# MOTORDEMO.net
KiCad netlist of a schematic drawn in Altium Designer
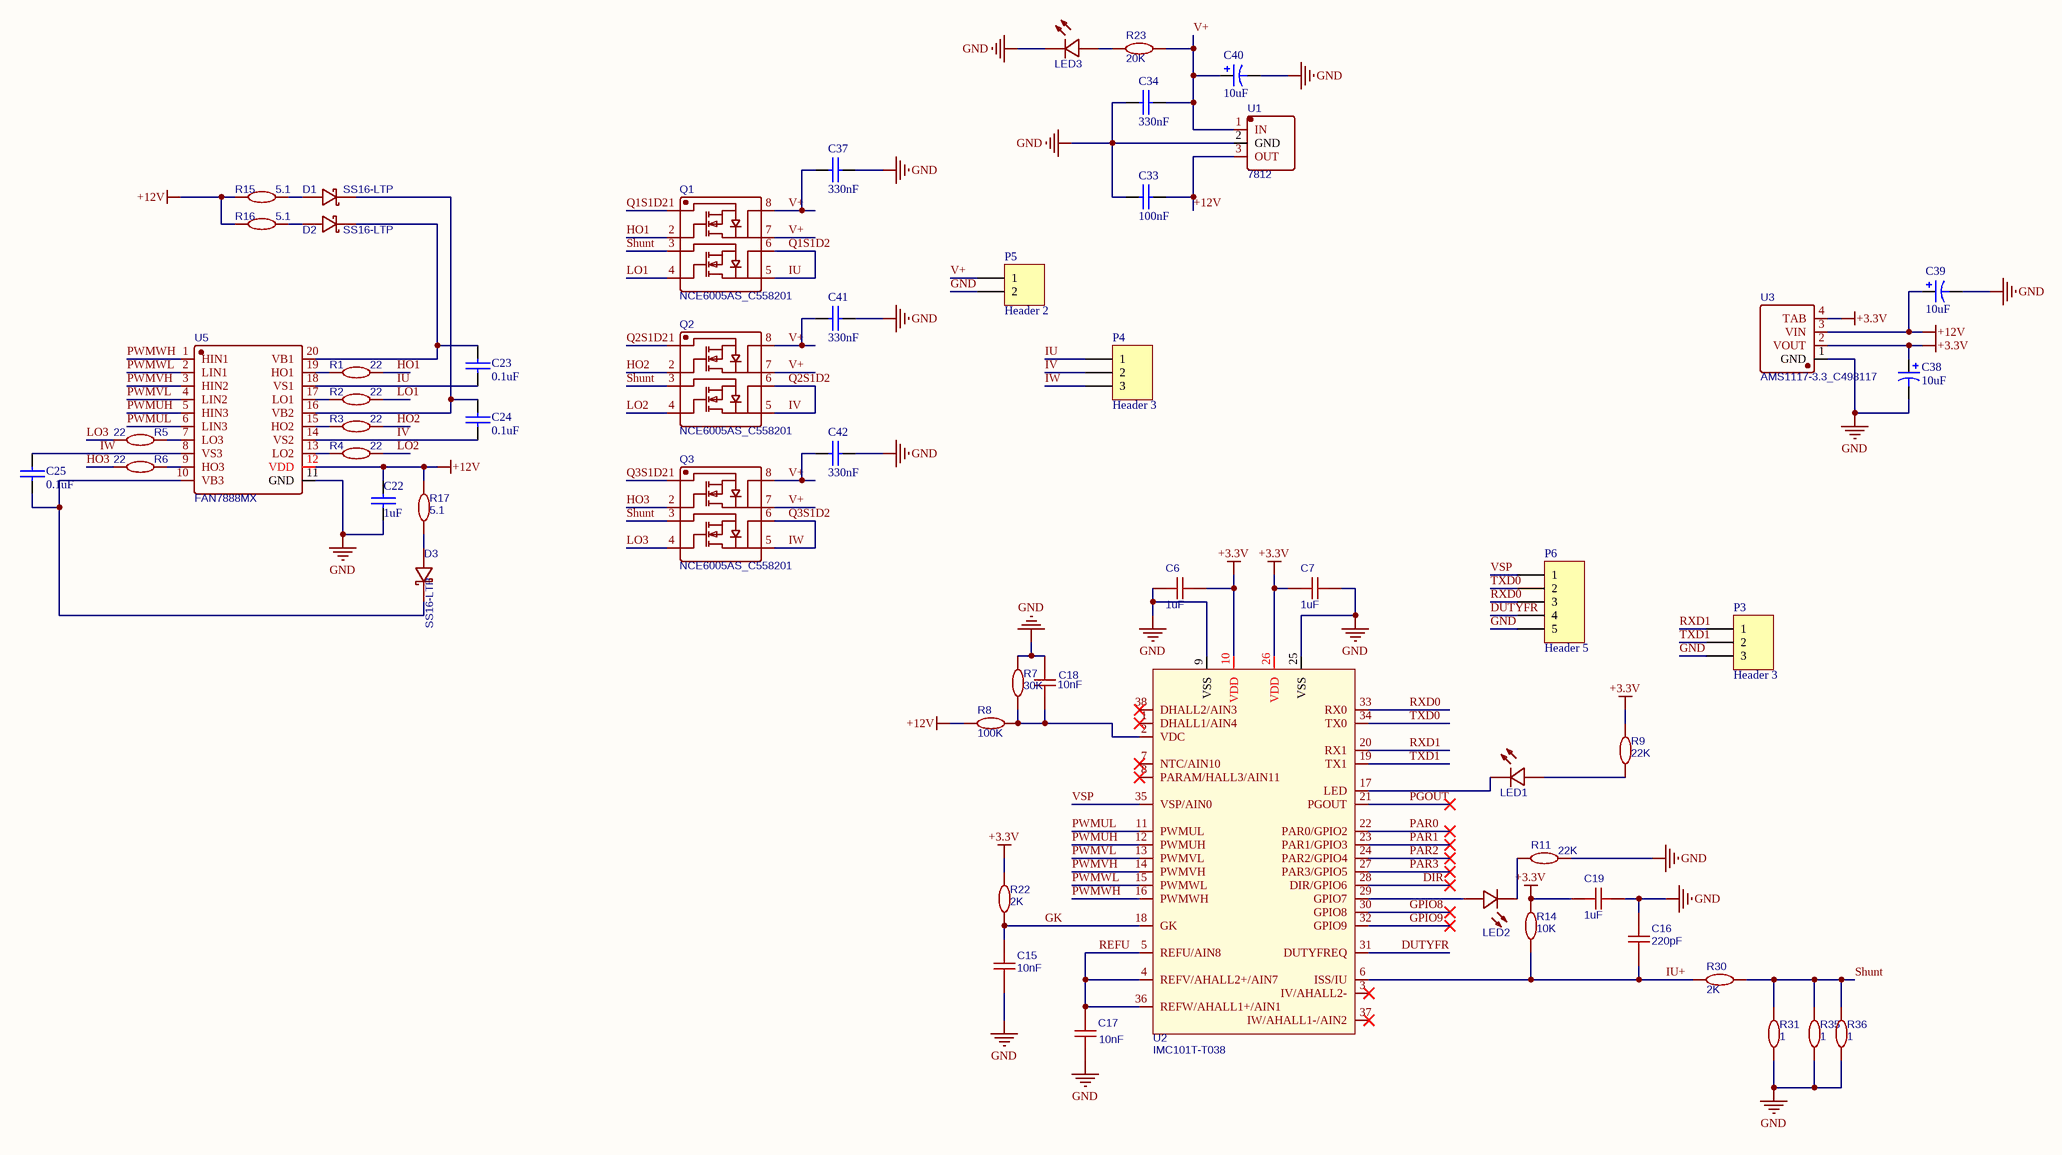
[diagram p0: MOTORDEMO.SchDoc]

(export (version "E")
  (design (tool "Eeschema 10.0.6"))
  (components
    (comp (ref "C6")
      (value "1uF")
      (footprint "C0603")
      (fields
        (field (name "BOM_MANUFACTURER PART") "CL10B104KC8NNNC")
        (field (name "BOM_SUPPLIER PART") "C15725")
      )
      (libsource (lib "motor") (part "100nF"))
    )
    (comp (ref "C7")
      (value "1uF")
      (footprint "C0603")
      (fields
        (field (name "BOM_MANUFACTURER PART") "CL10B104KC8NNNC")
        (field (name "BOM_SUPPLIER PART") "C15725")
      )
      (libsource (lib "motor") (part "100nF"))
    )
    (comp (ref "C15")
      (value "10nF")
      (footprint "C0603")
      (fields
        (field (name "BOM_MANUFACTURER PART") "CL10B104KC8NNNC")
        (field (name "BOM_SUPPLIER PART") "C15725")
      )
      (libsource (lib "motor") (part "100nF"))
    )
    (comp (ref "C16")
      (value "220pF")
      (footprint "C0603")
      (fields
        (field (name "BOM_MANUFACTURER PART") "CL10B104KC8NNNC")
        (field (name "BOM_SUPPLIER PART") "C15725")
      )
      (libsource (lib "motor") (part "100nF"))
    )
    (comp (ref "C17")
      (value "10nF")
      (footprint "C0603")
      (fields
        (field (name "BOM_MANUFACTURER PART") "CL10B104KC8NNNC")
        (field (name "BOM_SUPPLIER PART") "C15725")
      )
      (libsource (lib "motor") (part "100nF"))
    )
    (comp (ref "C18")
      (value "10nF")
      (footprint "C0603")
      (fields
        (field (name "BOM_MANUFACTURER PART") "CL10B104KC8NNNC")
        (field (name "BOM_SUPPLIER PART") "C15725")
      )
      (libsource (lib "motor") (part "100nF"))
    )
    (comp (ref "C19")
      (value "1uF")
      (footprint "C0603")
      (fields
        (field (name "BOM_MANUFACTURER PART") "CL10B104KC8NNNC")
        (field (name "BOM_SUPPLIER PART") "C15725")
      )
      (libsource (lib "motor") (part "100nF"))
    )
    (comp (ref "C22")
      (value "1uF")
      (footprint "C 0603_L")
      (description "Capacitor")
      (libsource (lib "原理图库") (part "CAP"))
    )
    (comp (ref "C23")
      (value "0.1uF")
      (footprint "C 0603_L")
      (description "Capacitor")
      (libsource (lib "原理图库") (part "CAP"))
    )
    (comp (ref "C24")
      (value "0.1uF")
      (footprint "C 0603_L")
      (description "Capacitor")
      (libsource (lib "原理图库") (part "CAP"))
    )
    (comp (ref "C25")
      (value "0.1uF")
      (footprint "C 0603_L")
      (description "Capacitor")
      (libsource (lib "原理图库") (part "CAP"))
    )
    (comp (ref "C33")
      (value "100nF")
      (footprint "C 0603_L")
      (description "Capacitor")
      (libsource (lib "原理图库") (part "CAP"))
    )
    (comp (ref "C34")
      (value "330nF")
      (footprint "C 0603_L")
      (description "Capacitor")
      (libsource (lib "原理图库") (part "CAP"))
    )
    (comp (ref "C37")
      (value "330nF")
      (footprint "C 0603_L")
      (description "Capacitor")
      (libsource (lib "原理图库") (part "CAP"))
    )
    (comp (ref "C38")
      (value "10uF")
      (footprint "10uF,35V,cap4*5.4")
      (description "Polarized Capacitor (Surface Mount)")
      (fields (field (name "PUBLISHER") "Altium Limited"))
      (libsource (lib "Miscellaneous Devices") (part "Cap Pol3"))
    )
    (comp (ref "C39")
      (value "10uF")
      (footprint "10uF,35V,cap4*5.4")
      (description "Polarized Capacitor (Surface Mount)")
      (fields (field (name "PUBLISHER") "Altium Limited"))
      (libsource (lib "Miscellaneous Devices") (part "Cap Pol3"))
    )
    (comp (ref "C40")
      (value "10uF")
      (footprint "10uF,35V,cap4*5.4")
      (description "Polarized Capacitor (Surface Mount)")
      (fields (field (name "PUBLISHER") "Altium Limited"))
      (libsource (lib "Miscellaneous Devices") (part "Cap Pol3"))
    )
    (comp (ref "C41")
      (value "330nF")
      (footprint "C 0603_L")
      (description "Capacitor")
      (libsource (lib "原理图库") (part "CAP"))
    )
    (comp (ref "C42")
      (value "330nF")
      (footprint "C 0603_L")
      (description "Capacitor")
      (libsource (lib "原理图库") (part "CAP"))
    )
    (comp (ref "D1")
      (value "SS16-LTP")
      (footprint "LL-34_L3.5-W1.5-RD")
      (fields (field (name "BOM_SUPPLIER PART") "C85689"))
      (libsource (lib "motordemo") (part "SS16-LTP"))
    )
    (comp (ref "D2")
      (value "SS16-LTP")
      (footprint "LL-34_L3.5-W1.5-RD")
      (fields (field (name "BOM_SUPPLIER PART") "C85689"))
      (libsource (lib "motordemo") (part "SS16-LTP"))
    )
    (comp (ref "D3")
      (value "SS16-LTP")
      (footprint "LL-34_L3.5-W1.5-RD")
      (fields (field (name "BOM_SUPPLIER PART") "C85689"))
      (libsource (lib "motordemo") (part "SS16-LTP"))
    )
    (comp (ref "LED1")
      (value "LED")
      (footprint "LED0603-R-RD")
      (fields
        (field (name "BOM_SUPPLIER PART") "C181863")
        (field (name "BOM_MANUFACTURER PART") "19-213/R6W-BP2Q2B/3T")
        (field (name "CONTRIBUTOR") "LCSC")
      )
      (libsource (lib "motor") (part "LED"))
    )
    (comp (ref "LED2")
      (value "LED")
      (footprint "LED0603-R-RD")
      (fields
        (field (name "BOM_SUPPLIER PART") "C181863")
        (field (name "BOM_MANUFACTURER PART") "19-213/R6W-BP2Q2B/3T")
        (field (name "CONTRIBUTOR") "LCSC")
      )
      (libsource (lib "motor") (part "LED"))
    )
    (comp (ref "LED3")
      (value "LED")
      (footprint "LED0603-R-RD")
      (fields
        (field (name "BOM_SUPPLIER PART") "C181863")
        (field (name "BOM_MANUFACTURER PART") "19-213/R6W-BP2Q2B/3T")
        (field (name "CONTRIBUTOR") "LCSC")
      )
      (libsource (lib "motor") (part "LED"))
    )
    (comp (ref "P3")
      (value "Header 3")
      (footprint "HDR1X3")
      (description "Header, 3-Pin")
      (fields (field (name "PUBLISHER") "Altium Limited"))
      (libsource (lib "Miscellaneous Connectors") (part "Header 3"))
    )
    (comp (ref "P4")
      (value "Header 3")
      (footprint "HDR1X3")
      (description "Header, 3-Pin")
      (fields (field (name "PUBLISHER") "Altium Limited"))
      (libsource (lib "Miscellaneous Connectors") (part "Header 3"))
    )
    (comp (ref "P5")
      (value "Header 2")
      (footprint "HDR1X2")
      (description "Header, 2-Pin")
      (fields (field (name "PUBLISHER") "Altium Limited"))
      (libsource (lib "Miscellaneous Connectors") (part "Header 2"))
    )
    (comp (ref "P6")
      (value "Header 5")
      (footprint "HDR1X5")
      (description "Header, 5-Pin")
      (fields (field (name "PUBLISHER") "Altium Limited"))
      (libsource (lib "Miscellaneous Connectors") (part "Header 5"))
    )
    (comp (ref "Q1")
      (value "NCE6005AS_C558201")
      (footprint "NCE6005AS")
      (fields
        (field (name "BOM_SUPPLIER PART") "C558201")
        (field (name "BOM_MANUFACTURER PART") "NCE6005AS")
        (field (name "CONTRIBUTOR") "LCSC")
      )
      (libsource (lib "motordemo") (part "NCE6005AS_C558201"))
    )
    (comp (ref "Q2")
      (value "NCE6005AS_C558201")
      (footprint "NCE6005AS")
      (fields
        (field (name "BOM_SUPPLIER PART") "C558201")
        (field (name "BOM_MANUFACTURER PART") "NCE6005AS")
        (field (name "CONTRIBUTOR") "LCSC")
      )
      (libsource (lib "motordemo") (part "NCE6005AS_C558201"))
    )
    (comp (ref "Q3")
      (value "NCE6005AS_C558201")
      (footprint "NCE6005AS")
      (fields
        (field (name "BOM_SUPPLIER PART") "C558201")
        (field (name "BOM_MANUFACTURER PART") "NCE6005AS")
        (field (name "CONTRIBUTOR") "LCSC")
      )
      (libsource (lib "motordemo") (part "NCE6005AS_C558201"))
    )
    (comp (ref "R1")
      (value "22")
      (footprint "R0603")
      (fields
        (field (name "BOM_SUPPLIER PART") "C327832")
        (field (name "BOM_MANUFACTURER PART") "MR06X105JTL")
        (field (name "CONTRIBUTOR") "LCSC")
      )
      (libsource (lib "motor") (part "1M"))
    )
    (comp (ref "R2")
      (value "22")
      (footprint "R0603")
      (fields
        (field (name "BOM_SUPPLIER PART") "C327832")
        (field (name "BOM_MANUFACTURER PART") "MR06X105JTL")
        (field (name "CONTRIBUTOR") "LCSC")
      )
      (libsource (lib "motor") (part "1M"))
    )
    (comp (ref "R3")
      (value "22")
      (footprint "R0603")
      (fields
        (field (name "BOM_SUPPLIER PART") "C327832")
        (field (name "BOM_MANUFACTURER PART") "MR06X105JTL")
        (field (name "CONTRIBUTOR") "LCSC")
      )
      (libsource (lib "motor") (part "1M"))
    )
    (comp (ref "R4")
      (value "22")
      (footprint "R0603")
      (fields
        (field (name "BOM_SUPPLIER PART") "C327832")
        (field (name "BOM_MANUFACTURER PART") "MR06X105JTL")
        (field (name "CONTRIBUTOR") "LCSC")
      )
      (libsource (lib "motor") (part "1M"))
    )
    (comp (ref "R5")
      (value "22")
      (footprint "R0603")
      (fields
        (field (name "BOM_SUPPLIER PART") "C327832")
        (field (name "BOM_MANUFACTURER PART") "MR06X105JTL")
        (field (name "CONTRIBUTOR") "LCSC")
      )
      (libsource (lib "motor") (part "1M"))
    )
    (comp (ref "R6")
      (value "22")
      (footprint "R0603")
      (fields
        (field (name "BOM_SUPPLIER PART") "C327832")
        (field (name "BOM_MANUFACTURER PART") "MR06X105JTL")
        (field (name "CONTRIBUTOR") "LCSC")
      )
      (libsource (lib "motor") (part "1M"))
    )
    (comp (ref "R7")
      (value "30K")
      (footprint "R0603")
      (fields
        (field (name "BOM_SUPPLIER PART") "C327832")
        (field (name "BOM_MANUFACTURER PART") "MR06X105JTL")
        (field (name "CONTRIBUTOR") "LCSC")
      )
      (libsource (lib "motor") (part "1M"))
    )
    (comp (ref "R8")
      (value "100K")
      (footprint "R0603")
      (fields
        (field (name "BOM_SUPPLIER PART") "C327832")
        (field (name "BOM_MANUFACTURER PART") "MR06X105JTL")
        (field (name "CONTRIBUTOR") "LCSC")
      )
      (libsource (lib "motor") (part "1M"))
    )
    (comp (ref "R9")
      (value "22K")
      (footprint "R0603")
      (fields
        (field (name "BOM_SUPPLIER PART") "C327832")
        (field (name "BOM_MANUFACTURER PART") "MR06X105JTL")
        (field (name "CONTRIBUTOR") "LCSC")
      )
      (libsource (lib "motor") (part "1M"))
    )
    (comp (ref "R11")
      (value "22K")
      (footprint "R0603")
      (fields
        (field (name "BOM_SUPPLIER PART") "C327832")
        (field (name "BOM_MANUFACTURER PART") "MR06X105JTL")
        (field (name "CONTRIBUTOR") "LCSC")
      )
      (libsource (lib "motor") (part "1M"))
    )
    (comp (ref "R14")
      (value "10K")
      (footprint "R0603")
      (fields
        (field (name "BOM_SUPPLIER PART") "C327832")
        (field (name "BOM_MANUFACTURER PART") "MR06X105JTL")
        (field (name "CONTRIBUTOR") "LCSC")
      )
      (libsource (lib "motor") (part "1M"))
    )
    (comp (ref "R15")
      (value "5.1")
      (footprint "R0603")
      (fields
        (field (name "BOM_SUPPLIER PART") "C327832")
        (field (name "BOM_MANUFACTURER PART") "MR06X105JTL")
        (field (name "CONTRIBUTOR") "LCSC")
      )
      (libsource (lib "motor") (part "1M"))
    )
    (comp (ref "R16")
      (value "5.1")
      (footprint "R0603")
      (fields
        (field (name "BOM_SUPPLIER PART") "C327832")
        (field (name "BOM_MANUFACTURER PART") "MR06X105JTL")
        (field (name "CONTRIBUTOR") "LCSC")
      )
      (libsource (lib "motor") (part "1M"))
    )
    (comp (ref "R17")
      (value "5.1")
      (footprint "R0603")
      (fields
        (field (name "BOM_SUPPLIER PART") "C327832")
        (field (name "BOM_MANUFACTURER PART") "MR06X105JTL")
        (field (name "CONTRIBUTOR") "LCSC")
      )
      (libsource (lib "motor") (part "1M"))
    )
    (comp (ref "R22")
      (value "2K")
      (footprint "R0603")
      (fields
        (field (name "BOM_SUPPLIER PART") "C327832")
        (field (name "BOM_MANUFACTURER PART") "MR06X105JTL")
        (field (name "CONTRIBUTOR") "LCSC")
      )
      (libsource (lib "motor") (part "1M"))
    )
    (comp (ref "R23")
      (value "20K")
      (footprint "R0603")
      (fields
        (field (name "BOM_SUPPLIER PART") "C327832")
        (field (name "BOM_MANUFACTURER PART") "MR06X105JTL")
        (field (name "CONTRIBUTOR") "LCSC")
      )
      (libsource (lib "motor") (part "1M"))
    )
    (comp (ref "R30")
      (value "2K")
      (footprint "R0603")
      (fields
        (field (name "BOM_SUPPLIER PART") "C327832")
        (field (name "BOM_MANUFACTURER PART") "MR06X105JTL")
        (field (name "CONTRIBUTOR") "LCSC")
      )
      (libsource (lib "motor") (part "1M"))
    )
    (comp (ref "R31")
      (value "1")
      (footprint "R1206")
      (fields
        (field (name "BOM_SUPPLIER PART") "C327832")
        (field (name "BOM_MANUFACTURER PART") "MR06X105JTL")
        (field (name "CONTRIBUTOR") "LCSC")
      )
      (libsource (lib "motor") (part "1M"))
    )
    (comp (ref "R35")
      (value "1")
      (footprint "R1206")
      (fields
        (field (name "BOM_SUPPLIER PART") "C327832")
        (field (name "BOM_MANUFACTURER PART") "MR06X105JTL")
        (field (name "CONTRIBUTOR") "LCSC")
      )
      (libsource (lib "motor") (part "1M"))
    )
    (comp (ref "R36")
      (value "1")
      (footprint "R1206")
      (fields
        (field (name "BOM_SUPPLIER PART") "C327832")
        (field (name "BOM_MANUFACTURER PART") "MR06X105JTL")
        (field (name "CONTRIBUTOR") "LCSC")
      )
      (libsource (lib "motor") (part "1M"))
    )
    (comp (ref "U1")
      (value "7812")
      (footprint "TO-220-3_L10.0-W4.5-P2.54-L")
      (fields (field (name "BOM_SUPPLIER PART") "C358369") (field (name "CONTRIBUTOR") "LCSC"))
      (libsource (lib "motordemo") (part "7812"))
    )
    (comp (ref "U2")
      (value "IMC101T-T038")
      (footprint "IMC101T-T038")
      (fields (field (name "BOM_SUPPLIER PART") "C536267") (field (name "CONTRIBUTOR") "LCSC"))
      (libsource (lib "motor") (part "IMC101T-T038"))
    )
    (comp (ref "U3")
      (value "AMS1117-3.3_C498117")
      (footprint "PG-SOT223-4_L6.5-W3.5-P2.30-LS7.0-BR")
      (fields
        (field (name "BOM_SUPPLIER PART") "C498117")
        (field (name "BOM_MANUFACTURER PART") "AMS1117-3.3")
        (field (name "CONTRIBUTOR") "LCSC")
      )
      (libsource (lib "20200123") (part "AMS1117-3.3_C498117"))
    )
    (comp (ref "U5")
      (value "FAN7888MX")
      (footprint "FAN7888")
      (fields (field (name "BOM_SUPPLIER PART") "C258167") (field (name "CONTRIBUTOR") "LCSC"))
      (libsource (lib "motordemo") (part "FAN7888MX"))
    )
  )
  (nets
    (net (code "1") (name "+3.3V") (class "Default")
      (node (ref "C19") (pin "1") (pinfunction "1_1") (pintype "passive"))
      (node (ref "C38") (pin "1") (pinfunction "1_1") (pintype "passive"))
      (node (ref "C6") (pin "1") (pinfunction "1_1") (pintype "passive"))
      (node (ref "C7") (pin "2") (pinfunction "2_2") (pintype "passive"))
      (node (ref "R14") (pin "1") (pinfunction "1_1") (pintype "passive"))
      (node (ref "R22") (pin "1") (pinfunction "1_1") (pintype "passive"))
      (node (ref "R9") (pin "2") (pinfunction "2_2") (pintype "passive"))
      (node (ref "U2") (pin "10") (pinfunction "VDD_10") (pintype "passive"))
      (node (ref "U2") (pin "26") (pinfunction "VDD_26") (pintype "passive"))
      (node (ref "U3") (pin "2") (pinfunction "VOUT_2") (pintype "passive"))
      (node (ref "U3") (pin "4") (pinfunction "TAB_4") (pintype "passive"))
    )
    (net (code "2") (name "+12V") (class "Default")
      (node (ref "C22") (pin "2") (pinfunction "2_2") (pintype "passive"))
      (node (ref "C33") (pin "1") (pinfunction "1_1") (pintype "passive"))
      (node (ref "C39") (pin "1") (pinfunction "1_1") (pintype "passive"))
      (node (ref "R15") (pin "2") (pinfunction "2_2") (pintype "passive"))
      (node (ref "R16") (pin "2") (pinfunction "2_2") (pintype "passive"))
      (node (ref "R17") (pin "1") (pinfunction "1_1") (pintype "passive"))
      (node (ref "R8") (pin "2") (pinfunction "2_2") (pintype "passive"))
      (node (ref "U1") (pin "3") (pinfunction "OUT_3") (pintype "passive"))
      (node (ref "U3") (pin "3") (pinfunction "VIN_3") (pintype "passive"))
      (node (ref "U5") (pin "12") (pinfunction "VDD_12") (pintype "passive"))
    )
    (net (code "3") (name "/DIR") (class "Default")
      (node (ref "U2") (pin "28") (pinfunction "DIR/GPIO6_28") (pintype "passive+no_connect"))
    )
    (net (code "4") (name "/DUTYFR") (class "Default")
      (node (ref "P6") (pin "4") (pinfunction "4_4") (pintype "passive"))
      (node (ref "U2") (pin "31") (pinfunction "DUTYFREQ_31") (pintype "passive"))
    )
    (net (code "5") (name "/GK") (class "Default")
      (node (ref "C15") (pin "2") (pinfunction "2_2") (pintype "passive"))
      (node (ref "R22") (pin "2") (pinfunction "2_2") (pintype "passive"))
      (node (ref "U2") (pin "18") (pinfunction "GK_18") (pintype "passive"))
    )
    (net (code "6") (name "/GPIO8") (class "Default")
      (node (ref "U2") (pin "30") (pinfunction "GPIO8_30") (pintype "passive+no_connect"))
    )
    (net (code "7") (name "/GPIO9") (class "Default")
      (node (ref "U2") (pin "32") (pinfunction "GPIO9_32") (pintype "passive+no_connect"))
    )
    (net (code "8") (name "/HO1") (class "Default")
      (node (ref "Q1") (pin "2") (pinfunction "2_2") (pintype "passive"))
      (node (ref "R1") (pin "1") (pinfunction "1_1") (pintype "passive"))
    )
    (net (code "9") (name "/HO2") (class "Default")
      (node (ref "Q2") (pin "2") (pinfunction "2_2") (pintype "passive"))
      (node (ref "R3") (pin "1") (pinfunction "1_1") (pintype "passive"))
    )
    (net (code "10") (name "/HO3") (class "Default")
      (node (ref "Q3") (pin "2") (pinfunction "2_2") (pintype "passive"))
      (node (ref "R6") (pin "2") (pinfunction "2_2") (pintype "passive"))
    )
    (net (code "11") (name "/IU") (class "Default")
      (node (ref "C23") (pin "1") (pinfunction "1_1") (pintype "passive"))
      (node (ref "P4") (pin "1") (pinfunction "1_1") (pintype "passive"))
      (node (ref "Q1") (pin "1") (pinfunction "1_1") (pintype "passive"))
      (node (ref "Q1") (pin "5") (pinfunction "5_5") (pintype "passive"))
      (node (ref "Q1") (pin "6") (pinfunction "6_6") (pintype "passive"))
      (node (ref "U5") (pin "18") (pinfunction "VS1_18") (pintype "passive"))
    )
    (net (code "12") (name "/IU+") (class "Default")
      (node (ref "C16") (pin "1") (pinfunction "1_1") (pintype "passive"))
      (node (ref "R14") (pin "2") (pinfunction "2_2") (pintype "passive"))
      (node (ref "R30") (pin "1") (pinfunction "1_1") (pintype "passive"))
      (node (ref "U2") (pin "6") (pinfunction "ISS/IU_6") (pintype "passive"))
    )
    (net (code "13") (name "/IV") (class "Default")
      (node (ref "C24") (pin "1") (pinfunction "1_1") (pintype "passive"))
      (node (ref "P4") (pin "2") (pinfunction "2_2") (pintype "passive"))
      (node (ref "Q2") (pin "1") (pinfunction "1_1") (pintype "passive"))
      (node (ref "Q2") (pin "5") (pinfunction "5_5") (pintype "passive"))
      (node (ref "Q2") (pin "6") (pinfunction "6_6") (pintype "passive"))
      (node (ref "U5") (pin "14") (pinfunction "VS2_14") (pintype "passive"))
    )
    (net (code "14") (name "/IW") (class "Default")
      (node (ref "C25") (pin "2") (pinfunction "2_2") (pintype "passive"))
      (node (ref "P4") (pin "3") (pinfunction "3_3") (pintype "passive"))
      (node (ref "Q3") (pin "1") (pinfunction "1_1") (pintype "passive"))
      (node (ref "Q3") (pin "5") (pinfunction "5_5") (pintype "passive"))
      (node (ref "Q3") (pin "6") (pinfunction "6_6") (pintype "passive"))
      (node (ref "U5") (pin "8") (pinfunction "VS3_8") (pintype "passive"))
    )
    (net (code "15") (name "/LO1") (class "Default")
      (node (ref "Q1") (pin "4") (pinfunction "4_4") (pintype "passive"))
      (node (ref "R2") (pin "1") (pinfunction "1_1") (pintype "passive"))
    )
    (net (code "16") (name "/LO2") (class "Default")
      (node (ref "Q2") (pin "4") (pinfunction "4_4") (pintype "passive"))
      (node (ref "R4") (pin "1") (pinfunction "1_1") (pintype "passive"))
    )
    (net (code "17") (name "/LO3") (class "Default")
      (node (ref "Q3") (pin "4") (pinfunction "4_4") (pintype "passive"))
      (node (ref "R5") (pin "2") (pinfunction "2_2") (pintype "passive"))
    )
    (net (code "18") (name "/PAR0") (class "Default")
      (node (ref "U2") (pin "22") (pinfunction "PAR0/GPIO2_22") (pintype "passive+no_connect"))
    )
    (net (code "19") (name "/PAR1") (class "Default")
      (node (ref "U2") (pin "23") (pinfunction "PAR1/GPIO3_23") (pintype "passive+no_connect"))
    )
    (net (code "20") (name "/PAR2") (class "Default")
      (node (ref "U2") (pin "24") (pinfunction "PAR2/GPIO4_24") (pintype "passive+no_connect"))
    )
    (net (code "21") (name "/PAR3") (class "Default")
      (node (ref "U2") (pin "27") (pinfunction "PAR3/GPIO5_27") (pintype "passive+no_connect"))
    )
    (net (code "22") (name "/PGOUT") (class "Default")
      (node (ref "U2") (pin "21") (pinfunction "PGOUT_21") (pintype "passive+no_connect"))
    )
    (net (code "23") (name "/PWMUH") (class "Default")
      (node (ref "U2") (pin "12") (pinfunction "PWMUH_12") (pintype "passive"))
      (node (ref "U5") (pin "5") (pinfunction "HIN3_5") (pintype "passive"))
    )
    (net (code "24") (name "/PWMUL") (class "Default")
      (node (ref "U2") (pin "11") (pinfunction "PWMUL_11") (pintype "passive"))
      (node (ref "U5") (pin "6") (pinfunction "LIN3_6") (pintype "passive"))
    )
    (net (code "25") (name "/PWMVH") (class "Default")
      (node (ref "U2") (pin "14") (pinfunction "PWMVH_14") (pintype "passive"))
      (node (ref "U5") (pin "3") (pinfunction "HIN2_3") (pintype "passive"))
    )
    (net (code "26") (name "/PWMVL") (class "Default")
      (node (ref "U2") (pin "13") (pinfunction "PWMVL_13") (pintype "passive"))
      (node (ref "U5") (pin "4") (pinfunction "LIN2_4") (pintype "passive"))
    )
    (net (code "27") (name "/PWMWH") (class "Default")
      (node (ref "U2") (pin "16") (pinfunction "PWMWH_16") (pintype "passive"))
      (node (ref "U5") (pin "1") (pinfunction "HIN1_1") (pintype "passive"))
    )
    (net (code "28") (name "/PWMWL") (class "Default")
      (node (ref "U2") (pin "15") (pinfunction "PWMWL_15") (pintype "passive"))
      (node (ref "U5") (pin "2") (pinfunction "LIN1_2") (pintype "passive"))
    )
    (net (code "29") (name "/REFU") (class "Default")
      (node (ref "C17") (pin "2") (pinfunction "2_2") (pintype "passive"))
      (node (ref "U2") (pin "36") (pinfunction "REFW/AHALL1+/AIN1_36") (pintype "passive"))
      (node (ref "U2") (pin "4") (pinfunction "REFV/AHALL2+/AIN7_4") (pintype "passive"))
      (node (ref "U2") (pin "5") (pinfunction "REFU/AIN8_5") (pintype "passive"))
    )
    (net (code "30") (name "/RXD0") (class "Default")
      (node (ref "P6") (pin "3") (pinfunction "3_3") (pintype "passive"))
      (node (ref "U2") (pin "33") (pinfunction "RX0_33") (pintype "passive"))
    )
    (net (code "31") (name "/RXD1") (class "Default")
      (node (ref "P3") (pin "1") (pinfunction "1_1") (pintype "passive"))
      (node (ref "U2") (pin "20") (pinfunction "RX1_20") (pintype "passive"))
    )
    (net (code "32") (name "/Shunt") (class "Default")
      (node (ref "Q1") (pin "3") (pinfunction "3_3") (pintype "passive"))
      (node (ref "Q2") (pin "3") (pinfunction "3_3") (pintype "passive"))
      (node (ref "Q3") (pin "3") (pinfunction "3_3") (pintype "passive"))
      (node (ref "R30") (pin "2") (pinfunction "2_2") (pintype "passive"))
      (node (ref "R31") (pin "2") (pinfunction "2_2") (pintype "passive"))
      (node (ref "R35") (pin "2") (pinfunction "2_2") (pintype "passive"))
      (node (ref "R36") (pin "2") (pinfunction "2_2") (pintype "passive"))
    )
    (net (code "33") (name "/TXD0") (class "Default")
      (node (ref "P6") (pin "2") (pinfunction "2_2") (pintype "passive"))
      (node (ref "U2") (pin "34") (pinfunction "TX0_34") (pintype "passive"))
    )
    (net (code "34") (name "/TXD1") (class "Default")
      (node (ref "P3") (pin "2") (pinfunction "2_2") (pintype "passive"))
      (node (ref "U2") (pin "19") (pinfunction "TX1_19") (pintype "passive"))
    )
    (net (code "35") (name "/V+") (class "Default")
      (node (ref "C34") (pin "1") (pinfunction "1_1") (pintype "passive"))
      (node (ref "C37") (pin "2") (pinfunction "2_2") (pintype "passive"))
      (node (ref "C40") (pin "1") (pinfunction "1_1") (pintype "passive"))
      (node (ref "C41") (pin "2") (pinfunction "2_2") (pintype "passive"))
      (node (ref "C42") (pin "2") (pinfunction "2_2") (pintype "passive"))
      (node (ref "P5") (pin "1") (pinfunction "1_1") (pintype "passive"))
      (node (ref "Q1") (pin "7") (pinfunction "7_7") (pintype "passive"))
      (node (ref "Q1") (pin "8") (pinfunction "8_8") (pintype "passive"))
      (node (ref "Q2") (pin "7") (pinfunction "7_7") (pintype "passive"))
      (node (ref "Q2") (pin "8") (pinfunction "8_8") (pintype "passive"))
      (node (ref "Q3") (pin "7") (pinfunction "7_7") (pintype "passive"))
      (node (ref "Q3") (pin "8") (pinfunction "8_8") (pintype "passive"))
      (node (ref "R23") (pin "1") (pinfunction "1_1") (pintype "passive"))
      (node (ref "U1") (pin "1") (pinfunction "IN_1") (pintype "passive"))
    )
    (net (code "36") (name "/VSP") (class "Default")
      (node (ref "P6") (pin "1") (pinfunction "1_1") (pintype "passive"))
      (node (ref "U2") (pin "35") (pinfunction "VSP/AIN0_35") (pintype "passive"))
    )
    (net (code "37") (name "GND") (class "Default")
      (node (ref "C15") (pin "1") (pinfunction "1_1") (pintype "passive"))
      (node (ref "C16") (pin "2") (pinfunction "2_2") (pintype "passive"))
      (node (ref "C17") (pin "1") (pinfunction "1_1") (pintype "passive"))
      (node (ref "C18") (pin "2") (pinfunction "2_2") (pintype "passive"))
      (node (ref "C19") (pin "2") (pinfunction "2_2") (pintype "passive"))
      (node (ref "C22") (pin "1") (pinfunction "1_1") (pintype "passive"))
      (node (ref "C33") (pin "2") (pinfunction "2_2") (pintype "passive"))
      (node (ref "C34") (pin "2") (pinfunction "2_2") (pintype "passive"))
      (node (ref "C37") (pin "1") (pinfunction "1_1") (pintype "passive"))
      (node (ref "C38") (pin "2") (pinfunction "2_2") (pintype "passive"))
      (node (ref "C39") (pin "2") (pinfunction "2_2") (pintype "passive"))
      (node (ref "C40") (pin "2") (pinfunction "2_2") (pintype "passive"))
      (node (ref "C41") (pin "1") (pinfunction "1_1") (pintype "passive"))
      (node (ref "C42") (pin "1") (pinfunction "1_1") (pintype "passive"))
      (node (ref "C6") (pin "2") (pinfunction "2_2") (pintype "passive"))
      (node (ref "C7") (pin "1") (pinfunction "1_1") (pintype "passive"))
      (node (ref "LED3") (pin "2") (pinfunction "2_2") (pintype "passive"))
      (node (ref "P3") (pin "3") (pinfunction "3_3") (pintype "passive"))
      (node (ref "P5") (pin "2") (pinfunction "2_2") (pintype "passive"))
      (node (ref "P6") (pin "5") (pinfunction "5_5") (pintype "passive"))
      (node (ref "R11") (pin "1") (pinfunction "1_1") (pintype "passive"))
      (node (ref "R31") (pin "1") (pinfunction "1_1") (pintype "passive"))
      (node (ref "R35") (pin "1") (pinfunction "1_1") (pintype "passive"))
      (node (ref "R36") (pin "1") (pinfunction "1_1") (pintype "passive"))
      (node (ref "R7") (pin "1") (pinfunction "1_1") (pintype "passive"))
      (node (ref "U1") (pin "2") (pinfunction "GND_2") (pintype "passive"))
      (node (ref "U2") (pin "25") (pinfunction "VSS_25") (pintype "passive"))
      (node (ref "U2") (pin "9") (pinfunction "VSS_9") (pintype "passive"))
      (node (ref "U3") (pin "1") (pinfunction "GND_1") (pintype "passive"))
      (node (ref "U5") (pin "11") (pinfunction "GND_11") (pintype "passive"))
    )
    (net (code "38") (name "Net-(D1-A)") (class "Default")
      (node (ref "D1") (pin "2") (pinfunction "A_2") (pintype "passive"))
      (node (ref "R15") (pin "1") (pinfunction "1_1") (pintype "passive"))
    )
    (net (code "39") (name "Net-(D1-C)") (class "Default")
      (node (ref "C24") (pin "2") (pinfunction "2_2") (pintype "passive"))
      (node (ref "D1") (pin "1") (pinfunction "C_1") (pintype "passive"))
      (node (ref "U5") (pin "16") (pinfunction "VB2_16") (pintype "passive"))
    )
    (net (code "40") (name "Net-(D2-A)") (class "Default")
      (node (ref "D2") (pin "2") (pinfunction "A_2") (pintype "passive"))
      (node (ref "R16") (pin "1") (pinfunction "1_1") (pintype "passive"))
    )
    (net (code "41") (name "Net-(D2-C)") (class "Default")
      (node (ref "C23") (pin "2") (pinfunction "2_2") (pintype "passive"))
      (node (ref "D2") (pin "1") (pinfunction "C_1") (pintype "passive"))
      (node (ref "U5") (pin "20") (pinfunction "VB1_20") (pintype "passive"))
    )
    (net (code "42") (name "Net-(D3-A)") (class "Default")
      (node (ref "D3") (pin "2") (pinfunction "A_2") (pintype "passive"))
      (node (ref "R17") (pin "2") (pinfunction "2_2") (pintype "passive"))
    )
    (net (code "43") (name "Net-(D3-C)") (class "Default")
      (node (ref "C25") (pin "1") (pinfunction "1_1") (pintype "passive"))
      (node (ref "D3") (pin "1") (pinfunction "C_1") (pintype "passive"))
      (node (ref "U5") (pin "10") (pinfunction "VB3_10") (pintype "passive"))
    )
    (net (code "44") (name "Net-(LED1-Pad1)") (class "Default")
      (node (ref "LED1") (pin "1") (pinfunction "1_1") (pintype "passive"))
      (node (ref "R9") (pin "1") (pinfunction "1_1") (pintype "passive"))
    )
    (net (code "45") (name "Net-(LED2-Pad2)") (class "Default")
      (node (ref "LED2") (pin "2") (pinfunction "2_2") (pintype "passive"))
      (node (ref "R11") (pin "2") (pinfunction "2_2") (pintype "passive"))
    )
    (net (code "46") (name "Net-(LED3-Pad1)") (class "Default")
      (node (ref "LED3") (pin "1") (pinfunction "1_1") (pintype "passive"))
      (node (ref "R23") (pin "2") (pinfunction "2_2") (pintype "passive"))
    )
    (net (code "47") (name "Net-(U2-GPIO7)") (class "Default")
      (node (ref "LED2") (pin "1") (pinfunction "1_1") (pintype "passive"))
      (node (ref "U2") (pin "29") (pinfunction "GPIO7_29") (pintype "passive"))
    )
    (net (code "48") (name "Net-(U2-LED)") (class "Default")
      (node (ref "LED1") (pin "2") (pinfunction "2_2") (pintype "passive"))
      (node (ref "U2") (pin "17") (pinfunction "LED_17") (pintype "passive"))
    )
    (net (code "49") (name "Net-(U2-VDC)") (class "Default")
      (node (ref "C18") (pin "1") (pinfunction "1_1") (pintype "passive"))
      (node (ref "R7") (pin "2") (pinfunction "2_2") (pintype "passive"))
      (node (ref "R8") (pin "1") (pinfunction "1_1") (pintype "passive"))
      (node (ref "U2") (pin "2") (pinfunction "VDC_2") (pintype "passive"))
    )
    (net (code "50") (name "Net-(U5-HO1)") (class "Default")
      (node (ref "R1") (pin "2") (pinfunction "2_2") (pintype "passive"))
      (node (ref "U5") (pin "19") (pinfunction "HO1_19") (pintype "passive"))
    )
    (net (code "51") (name "Net-(U5-HO2)") (class "Default")
      (node (ref "R3") (pin "2") (pinfunction "2_2") (pintype "passive"))
      (node (ref "U5") (pin "15") (pinfunction "HO2_15") (pintype "passive"))
    )
    (net (code "52") (name "Net-(U5-HO3)") (class "Default")
      (node (ref "R6") (pin "1") (pinfunction "1_1") (pintype "passive"))
      (node (ref "U5") (pin "9") (pinfunction "HO3_9") (pintype "passive"))
    )
    (net (code "53") (name "Net-(U5-LO1)") (class "Default")
      (node (ref "R2") (pin "2") (pinfunction "2_2") (pintype "passive"))
      (node (ref "U5") (pin "17") (pinfunction "LO1_17") (pintype "passive"))
    )
    (net (code "54") (name "Net-(U5-LO2)") (class "Default")
      (node (ref "R4") (pin "2") (pinfunction "2_2") (pintype "passive"))
      (node (ref "U5") (pin "13") (pinfunction "LO2_13") (pintype "passive"))
    )
    (net (code "55") (name "Net-(U5-LO3)") (class "Default")
      (node (ref "R5") (pin "1") (pinfunction "1_1") (pintype "passive"))
      (node (ref "U5") (pin "7") (pinfunction "LO3_7") (pintype "passive"))
    )
    (net (code "56") (name "unconnected-(U2-DHALL1{slash}AIN4-Pad1)") (class "Default")
      (node (ref "U2") (pin "1") (pinfunction "DHALL1/AIN4_1") (pintype "passive+no_connect"))
    )
    (net (code "57") (name "unconnected-(U2-DHALL2{slash}AIN3-Pad38)") (class "Default")
      (node (ref "U2") (pin "38") (pinfunction "DHALL2/AIN3_38") (pintype "passive+no_connect"))
    )
    (net (code "58") (name "unconnected-(U2-IV{slash}AHALL2--Pad3)") (class "Default")
      (node (ref "U2") (pin "3") (pinfunction "IV/AHALL2-_3") (pintype "passive+no_connect"))
    )
    (net (code "59") (name "unconnected-(U2-IW{slash}AHALL1-{slash}AIN2-Pad37)") (class "Default")
      (node (ref "U2") (pin "37") (pinfunction "IW/AHALL1-/AIN2_37") (pintype "passive+no_connect"))
    )
    (net (code "60") (name "unconnected-(U2-NTC{slash}AIN10-Pad7)") (class "Default")
      (node (ref "U2") (pin "7") (pinfunction "NTC/AIN10_7") (pintype "passive+no_connect"))
    )
    (net (code "61") (name "unconnected-(U2-PARAM{slash}HALL3{slash}AIN11-Pad8)") (class "Default")
      (node (ref "U2") (pin "8") (pinfunction "PARAM/HALL3/AIN11_8") (pintype "passive+no_connect"))
    )
  )
)
